# Harness_robottino_schem.net
KiCad netlist of a schematic drawn in Altium Designer
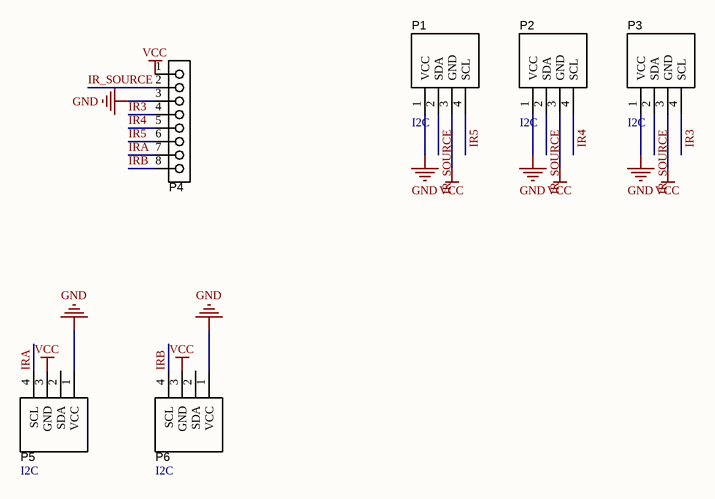
[diagram p0: Harness_robottino_schem.SchDoc]

(export (version "E")
  (design (tool "Eeschema 10.0.6"))
  (components
    (comp (ref "P1")
      (value "I2C")
      (footprint "TYCO/215079-4")
      (description "Micromatch I2C Connector")
      (libsource (lib "andylib") (part "Micromatch-I2C"))
    )
    (comp (ref "P2")
      (value "I2C")
      (footprint "TYCO/215079-4")
      (description "Micromatch I2C Connector")
      (libsource (lib "andylib") (part "Micromatch-I2C"))
    )
    (comp (ref "P3")
      (value "I2C")
      (footprint "TYCO/215079-4")
      (description "Micromatch I2C Connector")
      (libsource (lib "andylib") (part "Micromatch-I2C"))
    )
    (comp (ref "P4")
      (value "Header 8")
      (footprint "TYCO/215079-8")
      (description "Header, 8-Pin")
      (fields (field (name "PUBLISHER") "Altium Limited"))
      (libsource (lib "andylib") (part "Header 8"))
    )
    (comp (ref "P5")
      (value "I2C")
      (footprint "TYCO/215079-4")
      (description "Micromatch I2C Connector")
      (libsource (lib "") (part "Micromatch-I2C_1"))
    )
    (comp (ref "P6")
      (value "I2C")
      (footprint "TYCO/215079-4")
      (description "Micromatch I2C Connector")
      (libsource (lib "") (part "Micromatch-I2C_1"))
    )
  )
  (nets
    (net (code "1") (name "/IR3") (class "Default")
      (node (ref "P3") (pin "4") (pinfunction "SCL_4") (pintype "passive"))
      (node (ref "P4") (pin "4") (pinfunction "4_4") (pintype "passive"))
    )
    (net (code "2") (name "/IR4") (class "Default")
      (node (ref "P2") (pin "4") (pinfunction "SCL_4") (pintype "passive"))
      (node (ref "P4") (pin "5") (pinfunction "5_5") (pintype "passive"))
    )
    (net (code "3") (name "/IR5") (class "Default")
      (node (ref "P1") (pin "4") (pinfunction "SCL_4") (pintype "passive"))
      (node (ref "P4") (pin "6") (pinfunction "6_6") (pintype "passive"))
    )
    (net (code "4") (name "/IRA") (class "Default")
      (node (ref "P4") (pin "7") (pinfunction "7_7") (pintype "passive"))
      (node (ref "P5") (pin "4") (pinfunction "SCL_4") (pintype "passive"))
    )
    (net (code "5") (name "/IRB") (class "Default")
      (node (ref "P4") (pin "8") (pinfunction "8_8") (pintype "passive"))
      (node (ref "P6") (pin "4") (pinfunction "SCL_4") (pintype "passive"))
    )
    (net (code "6") (name "/IR_SOURCE") (class "Default")
      (node (ref "P1") (pin "2") (pinfunction "SDA_2") (pintype "passive"))
      (node (ref "P2") (pin "2") (pinfunction "SDA_2") (pintype "passive"))
      (node (ref "P3") (pin "2") (pinfunction "SDA_2") (pintype "passive"))
      (node (ref "P4") (pin "2") (pinfunction "2_2") (pintype "passive"))
    )
    (net (code "7") (name "GND") (class "Default")
      (node (ref "P1") (pin "1") (pinfunction "VCC_1") (pintype "passive"))
      (node (ref "P2") (pin "1") (pinfunction "VCC_1") (pintype "passive"))
      (node (ref "P3") (pin "1") (pinfunction "VCC_1") (pintype "passive"))
      (node (ref "P4") (pin "3") (pinfunction "3_3") (pintype "passive"))
      (node (ref "P5") (pin "1") (pinfunction "VCC_1") (pintype "passive"))
      (node (ref "P6") (pin "1") (pinfunction "VCC_1") (pintype "passive"))
    )
    (net (code "8") (name "VCC") (class "Default")
      (node (ref "P1") (pin "3") (pinfunction "GND_3") (pintype "passive"))
      (node (ref "P2") (pin "3") (pinfunction "GND_3") (pintype "passive"))
      (node (ref "P3") (pin "3") (pinfunction "GND_3") (pintype "passive"))
      (node (ref "P4") (pin "1") (pinfunction "1_1") (pintype "passive"))
      (node (ref "P5") (pin "3") (pinfunction "GND_3") (pintype "passive"))
      (node (ref "P6") (pin "3") (pinfunction "GND_3") (pintype "passive"))
    )
    (net (code "9") (name "unconnected-(P5-SDA-Pad2)") (class "Default")
      (node (ref "P5") (pin "2") (pinfunction "SDA_2") (pintype "passive"))
    )
    (net (code "10") (name "unconnected-(P6-SDA-Pad2)") (class "Default")
      (node (ref "P6") (pin "2") (pinfunction "SDA_2") (pintype "passive"))
    )
  )
)
